# punto5sq.net
KiCad netlist of a schematic drawn in Altium Designer
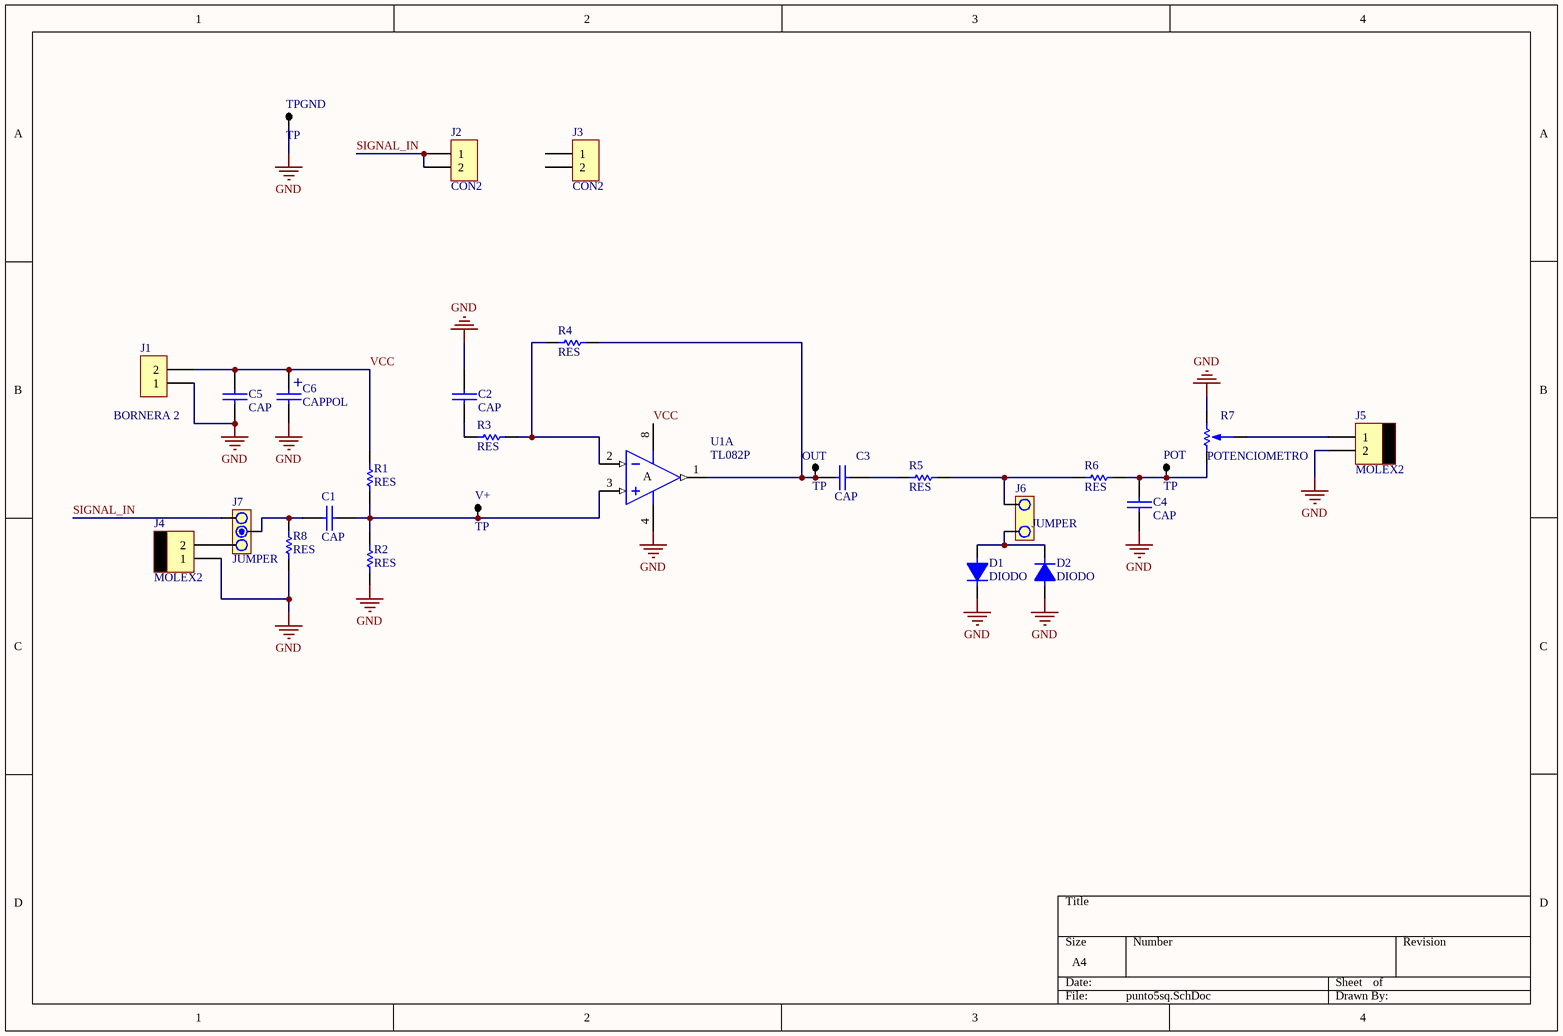
[diagram p0: punto5sq.SchDoc]

(export (version "E")
  (design (tool "Eeschema 10.0.6"))
  (components
    (comp (ref "C1") (value "CAP") (footprint "CAP200") (libsource (lib "LIBEBAL") (part "CAP")))
    (comp (ref "C2") (value "CAP") (footprint "CAP200") (libsource (lib "LIBEBAL") (part "CAP")))
    (comp (ref "C3") (value "CAP") (footprint "CAP200") (libsource (lib "LIBEBAL") (part "CAP")))
    (comp (ref "C4") (value "CAP") (footprint "CAP200") (libsource (lib "LIBEBAL") (part "CAP")))
    (comp (ref "C5") (value "CAP") (footprint "CAP200") (libsource (lib "LIBEBAL") (part "CAP")))
    (comp (ref "C6") (value "CAPPOL") (footprint "CAP100RP") (libsource (lib "LIBEBAL") (part "CAPPOL")))
    (comp (ref "D1") (value "DIODO") (footprint "DO41") (libsource (lib "LIBEBAL") (part "DIODO")))
    (comp (ref "D2") (value "DIODO") (footprint "DO41") (libsource (lib "LIBEBAL") (part "DIODO")))
    (comp (ref "J1")
      (value "BORNERA 2")
      (footprint "BORNERA2")
      (libsource (lib "LIBEBAL") (part "BORNERA 2"))
    )
    (comp (ref "J2") (value "CON2") (footprint "SIP2") (libsource (lib "LIBEBAL") (part "CON2")))
    (comp (ref "J3") (value "CON2") (footprint "SIP2") (libsource (lib "LIBEBAL") (part "CON2")))
    (comp (ref "J4") (value "MOLEX2") (footprint "MOLEX2") (libsource (lib "") (part "MOLEX2_1")))
    (comp (ref "J5") (value "MOLEX2") (footprint "MOLEX2") (libsource (lib "LIBEBAL") (part "MOLEX2")))
    (comp (ref "J6") (value "JUMPER") (footprint "JUMPER2") (libsource (lib "LIBEBAL") (part "JUMPER")))
    (comp (ref "J7") (value "JUMPER") (footprint "JUMPER3") (libsource (lib "LIBEBAL") (part "JUMPER3")))
    (comp (ref "OUT") (value "TP") (footprint "TPTH") (libsource (lib "LIBEBAL") (part "TP")))
    (comp (ref "POT") (value "TP") (footprint "TPTH") (libsource (lib "LIBEBAL") (part "TP")))
    (comp (ref "R1") (value "RES") (footprint "RES400") (libsource (lib "LIBEBAL") (part "RES")))
    (comp (ref "R2") (value "RES") (footprint "RES400") (libsource (lib "LIBEBAL") (part "RES")))
    (comp (ref "R3") (value "RES") (footprint "RES400") (libsource (lib "LIBEBAL") (part "RES")))
    (comp (ref "R4") (value "RES") (footprint "RES400") (libsource (lib "LIBEBAL") (part "RES")))
    (comp (ref "R5") (value "RES") (footprint "RES400") (libsource (lib "LIBEBAL") (part "RES")))
    (comp (ref "R6") (value "RES") (footprint "RES400") (libsource (lib "LIBEBAL") (part "RES")))
    (comp (ref "R7")
      (value "POTENCIOMETRO")
      (footprint "POTENCIOMETRO")
      (libsource (lib "LIBEBAL") (part "POTENCIOMETRO"))
    )
    (comp (ref "R8") (value "RES") (footprint "RES400") (libsource (lib "LIBEBAL") (part "RES")))
    (comp (ref "TPGND") (value "TP") (footprint "TPTH") (libsource (lib "LIBEBAL") (part "TP")))
    (comp (ref "U1")
      (value "TL082P")
      (footprint "P008")
      (description "JFET-Input Operational Amplifier")
      (fields (field (name "PUBLISHER") "Altium Limited"))
      (libsource (lib "TI Operational Amplifier") (part "TL082P"))
    )
    (comp (ref "V+") (value "TP") (footprint "TPTH") (libsource (lib "LIBEBAL") (part "TP")))
  )
  (nets
    (net (code "1") (name "/SIGNAL_IN") (class "Default")
      (node (ref "J2") (pin "1") (pinfunction "1_1") (pintype "passive"))
      (node (ref "J2") (pin "2") (pinfunction "2_2") (pintype "passive"))
      (node (ref "J7") (pin "3") (pinfunction "3_3") (pintype "passive"))
    )
    (net (code "2") (name "/VCC") (class "Default")
      (node (ref "C5") (pin "1") (pinfunction "1_1") (pintype "passive"))
      (node (ref "C6") (pin "1") (pinfunction "1_1") (pintype "passive"))
      (node (ref "J1") (pin "2") (pinfunction "2_2") (pintype "passive"))
      (node (ref "R1") (pin "2") (pinfunction "2_2") (pintype "passive"))
      (node (ref "U1") (pin "8") (pinfunction "V+_8") (pintype "power_in"))
    )
    (net (code "3") (name "GND") (class "Default")
      (node (ref "C2") (pin "2") (pinfunction "2_2") (pintype "passive"))
      (node (ref "C4") (pin "2") (pinfunction "2_2") (pintype "passive"))
      (node (ref "C5") (pin "2") (pinfunction "2_2") (pintype "passive"))
      (node (ref "C6") (pin "2") (pinfunction "2_2") (pintype "passive"))
      (node (ref "D1") (pin "2") (pinfunction "2_2") (pintype "passive"))
      (node (ref "D2") (pin "1") (pinfunction "1_1") (pintype "passive"))
      (node (ref "J1") (pin "1") (pinfunction "1_1") (pintype "passive"))
      (node (ref "J4") (pin "1") (pinfunction "1_1") (pintype "passive"))
      (node (ref "J5") (pin "2") (pinfunction "2_2") (pintype "passive"))
      (node (ref "R2") (pin "1") (pinfunction "1_1") (pintype "passive"))
      (node (ref "R7") (pin "1") (pinfunction "1_1") (pintype "passive"))
      (node (ref "R8") (pin "2") (pinfunction "2_2") (pintype "passive"))
      (node (ref "TPGND") (pin "1") (pinfunction "1_1") (pintype "passive"))
      (node (ref "U1") (pin "4") (pinfunction "V-_4") (pintype "power_in"))
    )
    (net (code "4") (name "Net-(C1-Pad2)") (class "Default")
      (node (ref "C1") (pin "2") (pinfunction "2_2") (pintype "passive"))
      (node (ref "J7") (pin "2") (pinfunction "2_2") (pintype "passive"))
      (node (ref "R8") (pin "1") (pinfunction "1_1") (pintype "passive"))
    )
    (net (code "5") (name "Net-(C2-Pad1)") (class "Default")
      (node (ref "C2") (pin "1") (pinfunction "1_1") (pintype "passive"))
      (node (ref "R3") (pin "1") (pinfunction "1_1") (pintype "passive"))
    )
    (net (code "6") (name "Net-(C3-Pad2)") (class "Default")
      (node (ref "C3") (pin "2") (pinfunction "2_2") (pintype "passive"))
      (node (ref "R5") (pin "1") (pinfunction "1_1") (pintype "passive"))
    )
    (net (code "7") (name "Net-(C4-Pad1)") (class "Default")
      (node (ref "C4") (pin "1") (pinfunction "1_1") (pintype "passive"))
      (node (ref "POT") (pin "1") (pinfunction "1_1") (pintype "passive"))
      (node (ref "R6") (pin "2") (pinfunction "2_2") (pintype "passive"))
      (node (ref "R7") (pin "3") (pinfunction "3_3") (pintype "passive"))
    )
    (net (code "8") (name "Net-(D1-Pad1)") (class "Default")
      (node (ref "D1") (pin "1") (pinfunction "1_1") (pintype "passive"))
      (node (ref "D2") (pin "2") (pinfunction "2_2") (pintype "passive"))
      (node (ref "J6") (pin "1") (pinfunction "1_1") (pintype "passive"))
    )
    (net (code "9") (name "Net-(J4-Pad2)") (class "Default")
      (node (ref "J4") (pin "2") (pinfunction "2_2") (pintype "passive"))
      (node (ref "J7") (pin "1") (pinfunction "1_1") (pintype "passive"))
    )
    (net (code "10") (name "Net-(J5-Pad1)") (class "Default")
      (node (ref "J5") (pin "1") (pinfunction "1_1") (pintype "passive"))
      (node (ref "R7") (pin "2") (pinfunction "2_2") (pintype "passive"))
    )
    (net (code "11") (name "Net-(J6-Pad2)") (class "Default")
      (node (ref "J6") (pin "2") (pinfunction "2_2") (pintype "passive"))
      (node (ref "R5") (pin "2") (pinfunction "2_2") (pintype "passive"))
      (node (ref "R6") (pin "1") (pinfunction "1_1") (pintype "passive"))
    )
    (net (code "12") (name "Net-(U1A-IN+)") (class "Default")
      (node (ref "C1") (pin "1") (pinfunction "1_1") (pintype "passive"))
      (node (ref "R1") (pin "1") (pinfunction "1_1") (pintype "passive"))
      (node (ref "R2") (pin "2") (pinfunction "2_2") (pintype "passive"))
      (node (ref "U1") (pin "3") (pinfunction "IN+_3") (pintype "input"))
      (node (ref "V+") (pin "1") (pinfunction "1_1") (pintype "passive"))
    )
    (net (code "13") (name "Net-(U1A-IN-)") (class "Default")
      (node (ref "R3") (pin "2") (pinfunction "2_2") (pintype "passive"))
      (node (ref "R4") (pin "1") (pinfunction "1_1") (pintype "passive"))
      (node (ref "U1") (pin "2") (pinfunction "IN-_2") (pintype "input"))
    )
    (net (code "14") (name "Net-(U1A-OUT)") (class "Default")
      (node (ref "C3") (pin "1") (pinfunction "1_1") (pintype "passive"))
      (node (ref "OUT") (pin "1") (pinfunction "1_1") (pintype "passive"))
      (node (ref "R4") (pin "2") (pinfunction "2_2") (pintype "passive"))
      (node (ref "U1") (pin "1") (pinfunction "OUT_1") (pintype "output"))
    )
    (net (code "15") (name "unconnected-(J3-Pad1)") (class "Default")
      (node (ref "J3") (pin "1") (pinfunction "1_1") (pintype "passive"))
    )
    (net (code "16") (name "unconnected-(J3-Pad2)") (class "Default")
      (node (ref "J3") (pin "2") (pinfunction "2_2") (pintype "passive"))
    )
  )
)
